# Action_Split.net
KiCad netlist of a schematic drawn in Altium Designer
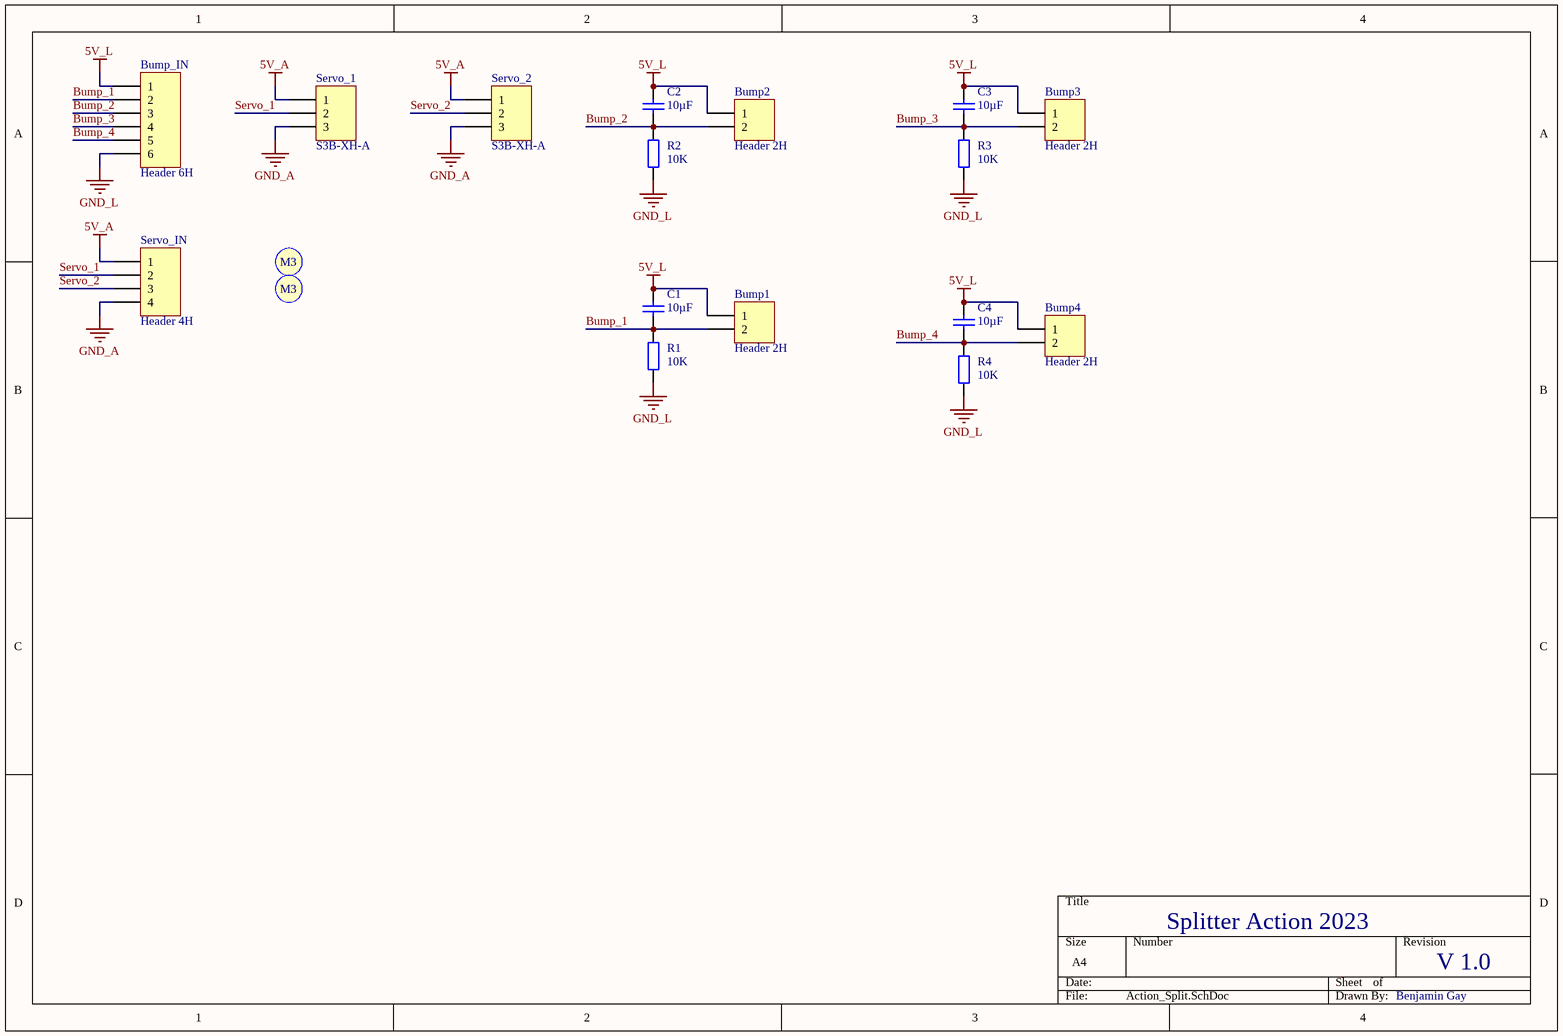
[diagram p0: Action_Split.SchDoc]

(export (version "E")
  (design (tool "Eeschema 10.0.6"))
  (components
    (comp (ref "Bump1")
      (value "Header 2H")
      (footprint "S2B-XH-A")
      (description "Header, 2-Pin, Right Angle")
      (fields (field (name "PUBLISHER") "Altium Limited"))
      (libsource (lib "Miscellaneous Connectors") (part "Header 2H"))
    )
    (comp (ref "Bump2")
      (value "Header 2H")
      (footprint "S2B-XH-A")
      (description "Header, 2-Pin, Right Angle")
      (fields (field (name "PUBLISHER") "Altium Limited"))
      (libsource (lib "Miscellaneous Connectors") (part "Header 2H"))
    )
    (comp (ref "Bump3")
      (value "Header 2H")
      (footprint "S2B-XH-A")
      (description "Header, 2-Pin, Right Angle")
      (fields (field (name "PUBLISHER") "Altium Limited"))
      (libsource (lib "Miscellaneous Connectors") (part "Header 2H"))
    )
    (comp (ref "Bump4")
      (value "Header 2H")
      (footprint "S2B-XH-A")
      (description "Header, 2-Pin, Right Angle")
      (fields (field (name "PUBLISHER") "Altium Limited"))
      (libsource (lib "Miscellaneous Connectors") (part "Header 2H"))
    )
    (comp (ref "Bump_IN")
      (value "Header 6H")
      (footprint "S6B-XH-A")
      (description "Header, 6-Pin, Right Angle")
      (fields (field (name "PUBLISHER") "Altium Limited"))
      (libsource (lib "Miscellaneous Connectors") (part "Header 6H"))
    )
    (comp (ref "C1")
      (value "10µF")
      (footprint "Capacitor 1206")
      (description "Capacitor")
      (fields (field (name "PUBLISHER") "Altium Limited"))
      (libsource (lib "Miscellaneous Devices") (part "Cap"))
    )
    (comp (ref "C2")
      (value "10µF")
      (footprint "Capacitor 1206")
      (description "Capacitor")
      (fields (field (name "PUBLISHER") "Altium Limited"))
      (libsource (lib "Miscellaneous Devices") (part "Cap"))
    )
    (comp (ref "C3")
      (value "10µF")
      (footprint "Capacitor 1206")
      (description "Capacitor")
      (fields (field (name "PUBLISHER") "Altium Limited"))
      (libsource (lib "Miscellaneous Devices") (part "Cap"))
    )
    (comp (ref "C4")
      (value "10µF")
      (footprint "Capacitor 1206")
      (description "Capacitor")
      (fields (field (name "PUBLISHER") "Altium Limited"))
      (libsource (lib "Miscellaneous Devices") (part "Cap"))
    )
    (comp (ref "R1")
      (value "10K")
      (footprint "Resistor 1206")
      (description "Resistor")
      (fields (field (name "Comment") "Res2") (field (name "PUBLISHER") "Altium Limited"))
      (libsource (lib "Miscellaneous Devices") (part "Res2"))
    )
    (comp (ref "R2")
      (value "10K")
      (footprint "Resistor 1206")
      (description "Resistor")
      (fields (field (name "Comment") "Res2") (field (name "PUBLISHER") "Altium Limited"))
      (libsource (lib "Miscellaneous Devices") (part "Res2"))
    )
    (comp (ref "R3")
      (value "10K")
      (footprint "Resistor 1206")
      (description "Resistor")
      (fields (field (name "Comment") "Res2") (field (name "PUBLISHER") "Altium Limited"))
      (libsource (lib "Miscellaneous Devices") (part "Res2"))
    )
    (comp (ref "R4")
      (value "10K")
      (footprint "Resistor 1206")
      (description "Resistor")
      (fields (field (name "Comment") "Res2") (field (name "PUBLISHER") "Altium Limited"))
      (libsource (lib "Miscellaneous Devices") (part "Res2"))
    )
    (comp (ref "S1")
      (value "Screw M3")
      (footprint "Screw M3")
      (libsource (lib "Robot_2019") (part "Screw M3"))
    )
    (comp (ref "S2")
      (value "Screw M3")
      (footprint "Screw M3")
      (libsource (lib "Robot_2019") (part "Screw M3"))
    )
    (comp (ref "Servo_1")
      (value "S3B-XH-A")
      (footprint "S3B-XH-A")
      (description "Header, 3-Pin, Right Angle")
      (fields (field (name "PUBLISHER") "Altium Limited"))
      (libsource (lib "Miscellaneous Connectors") (part "Header 3H"))
    )
    (comp (ref "Servo_2")
      (value "S3B-XH-A")
      (footprint "S3B-XH-A")
      (description "Header, 3-Pin, Right Angle")
      (fields (field (name "PUBLISHER") "Altium Limited"))
      (libsource (lib "Miscellaneous Connectors") (part "Header 3H"))
    )
    (comp (ref "Servo_IN")
      (value "Header 4H")
      (footprint "S4B-XH-A")
      (description "Header, 4-Pin, Right Angle")
      (fields (field (name "PUBLISHER") "Altium Limited"))
      (libsource (lib "Miscellaneous Connectors") (part "Header 4H"))
    )
  )
  (nets
    (net (code "1") (name "/Bump_1") (class "Default")
      (node (ref "Bump1") (pin "2") (pinfunction "2_2") (pintype "passive"))
      (node (ref "Bump_IN") (pin "2") (pinfunction "2_2") (pintype "passive"))
      (node (ref "C1") (pin "1") (pinfunction "1_1") (pintype "passive"))
      (node (ref "R1") (pin "2") (pinfunction "2_2") (pintype "passive"))
    )
    (net (code "2") (name "/Bump_2") (class "Default")
      (node (ref "Bump2") (pin "2") (pinfunction "2_2") (pintype "passive"))
      (node (ref "Bump_IN") (pin "3") (pinfunction "3_3") (pintype "passive"))
      (node (ref "C2") (pin "1") (pinfunction "1_1") (pintype "passive"))
      (node (ref "R2") (pin "2") (pinfunction "2_2") (pintype "passive"))
    )
    (net (code "3") (name "/Bump_3") (class "Default")
      (node (ref "Bump3") (pin "2") (pinfunction "2_2") (pintype "passive"))
      (node (ref "Bump_IN") (pin "4") (pinfunction "4_4") (pintype "passive"))
      (node (ref "C3") (pin "1") (pinfunction "1_1") (pintype "passive"))
      (node (ref "R3") (pin "2") (pinfunction "2_2") (pintype "passive"))
    )
    (net (code "4") (name "/Bump_4") (class "Default")
      (node (ref "Bump4") (pin "2") (pinfunction "2_2") (pintype "passive"))
      (node (ref "Bump_IN") (pin "5") (pinfunction "5_5") (pintype "passive"))
      (node (ref "C4") (pin "1") (pinfunction "1_1") (pintype "passive"))
      (node (ref "R4") (pin "2") (pinfunction "2_2") (pintype "passive"))
    )
    (net (code "5") (name "/Servo_1") (class "Default")
      (node (ref "Servo_1") (pin "2") (pinfunction "2_2") (pintype "passive"))
      (node (ref "Servo_IN") (pin "2") (pinfunction "2_2") (pintype "passive"))
    )
    (net (code "6") (name "/Servo_2") (class "Default")
      (node (ref "Servo_2") (pin "2") (pinfunction "2_2") (pintype "passive"))
      (node (ref "Servo_IN") (pin "3") (pinfunction "3_3") (pintype "passive"))
    )
    (net (code "7") (name "5V_A") (class "Default")
      (node (ref "Servo_1") (pin "1") (pinfunction "1_1") (pintype "passive"))
      (node (ref "Servo_2") (pin "1") (pinfunction "1_1") (pintype "passive"))
      (node (ref "Servo_IN") (pin "1") (pinfunction "1_1") (pintype "passive"))
    )
    (net (code "8") (name "5V_L") (class "Default")
      (node (ref "Bump1") (pin "1") (pinfunction "1_1") (pintype "passive"))
      (node (ref "Bump2") (pin "1") (pinfunction "1_1") (pintype "passive"))
      (node (ref "Bump3") (pin "1") (pinfunction "1_1") (pintype "passive"))
      (node (ref "Bump4") (pin "1") (pinfunction "1_1") (pintype "passive"))
      (node (ref "Bump_IN") (pin "1") (pinfunction "1_1") (pintype "passive"))
      (node (ref "C1") (pin "2") (pinfunction "2_2") (pintype "passive"))
      (node (ref "C2") (pin "2") (pinfunction "2_2") (pintype "passive"))
      (node (ref "C3") (pin "2") (pinfunction "2_2") (pintype "passive"))
      (node (ref "C4") (pin "2") (pinfunction "2_2") (pintype "passive"))
    )
    (net (code "9") (name "GND_A") (class "Default")
      (node (ref "Servo_1") (pin "3") (pinfunction "3_3") (pintype "passive"))
      (node (ref "Servo_2") (pin "3") (pinfunction "3_3") (pintype "passive"))
      (node (ref "Servo_IN") (pin "4") (pinfunction "4_4") (pintype "passive"))
    )
    (net (code "10") (name "GND_L") (class "Default")
      (node (ref "Bump_IN") (pin "6") (pinfunction "6_6") (pintype "passive"))
      (node (ref "R1") (pin "1") (pinfunction "1_1") (pintype "passive"))
      (node (ref "R2") (pin "1") (pinfunction "1_1") (pintype "passive"))
      (node (ref "R3") (pin "1") (pinfunction "1_1") (pintype "passive"))
      (node (ref "R4") (pin "1") (pinfunction "1_1") (pintype "passive"))
    )
  )
)
